# NeuronSynapseVersion3_1.net
KiCad netlist of a schematic drawn in Altium Designer
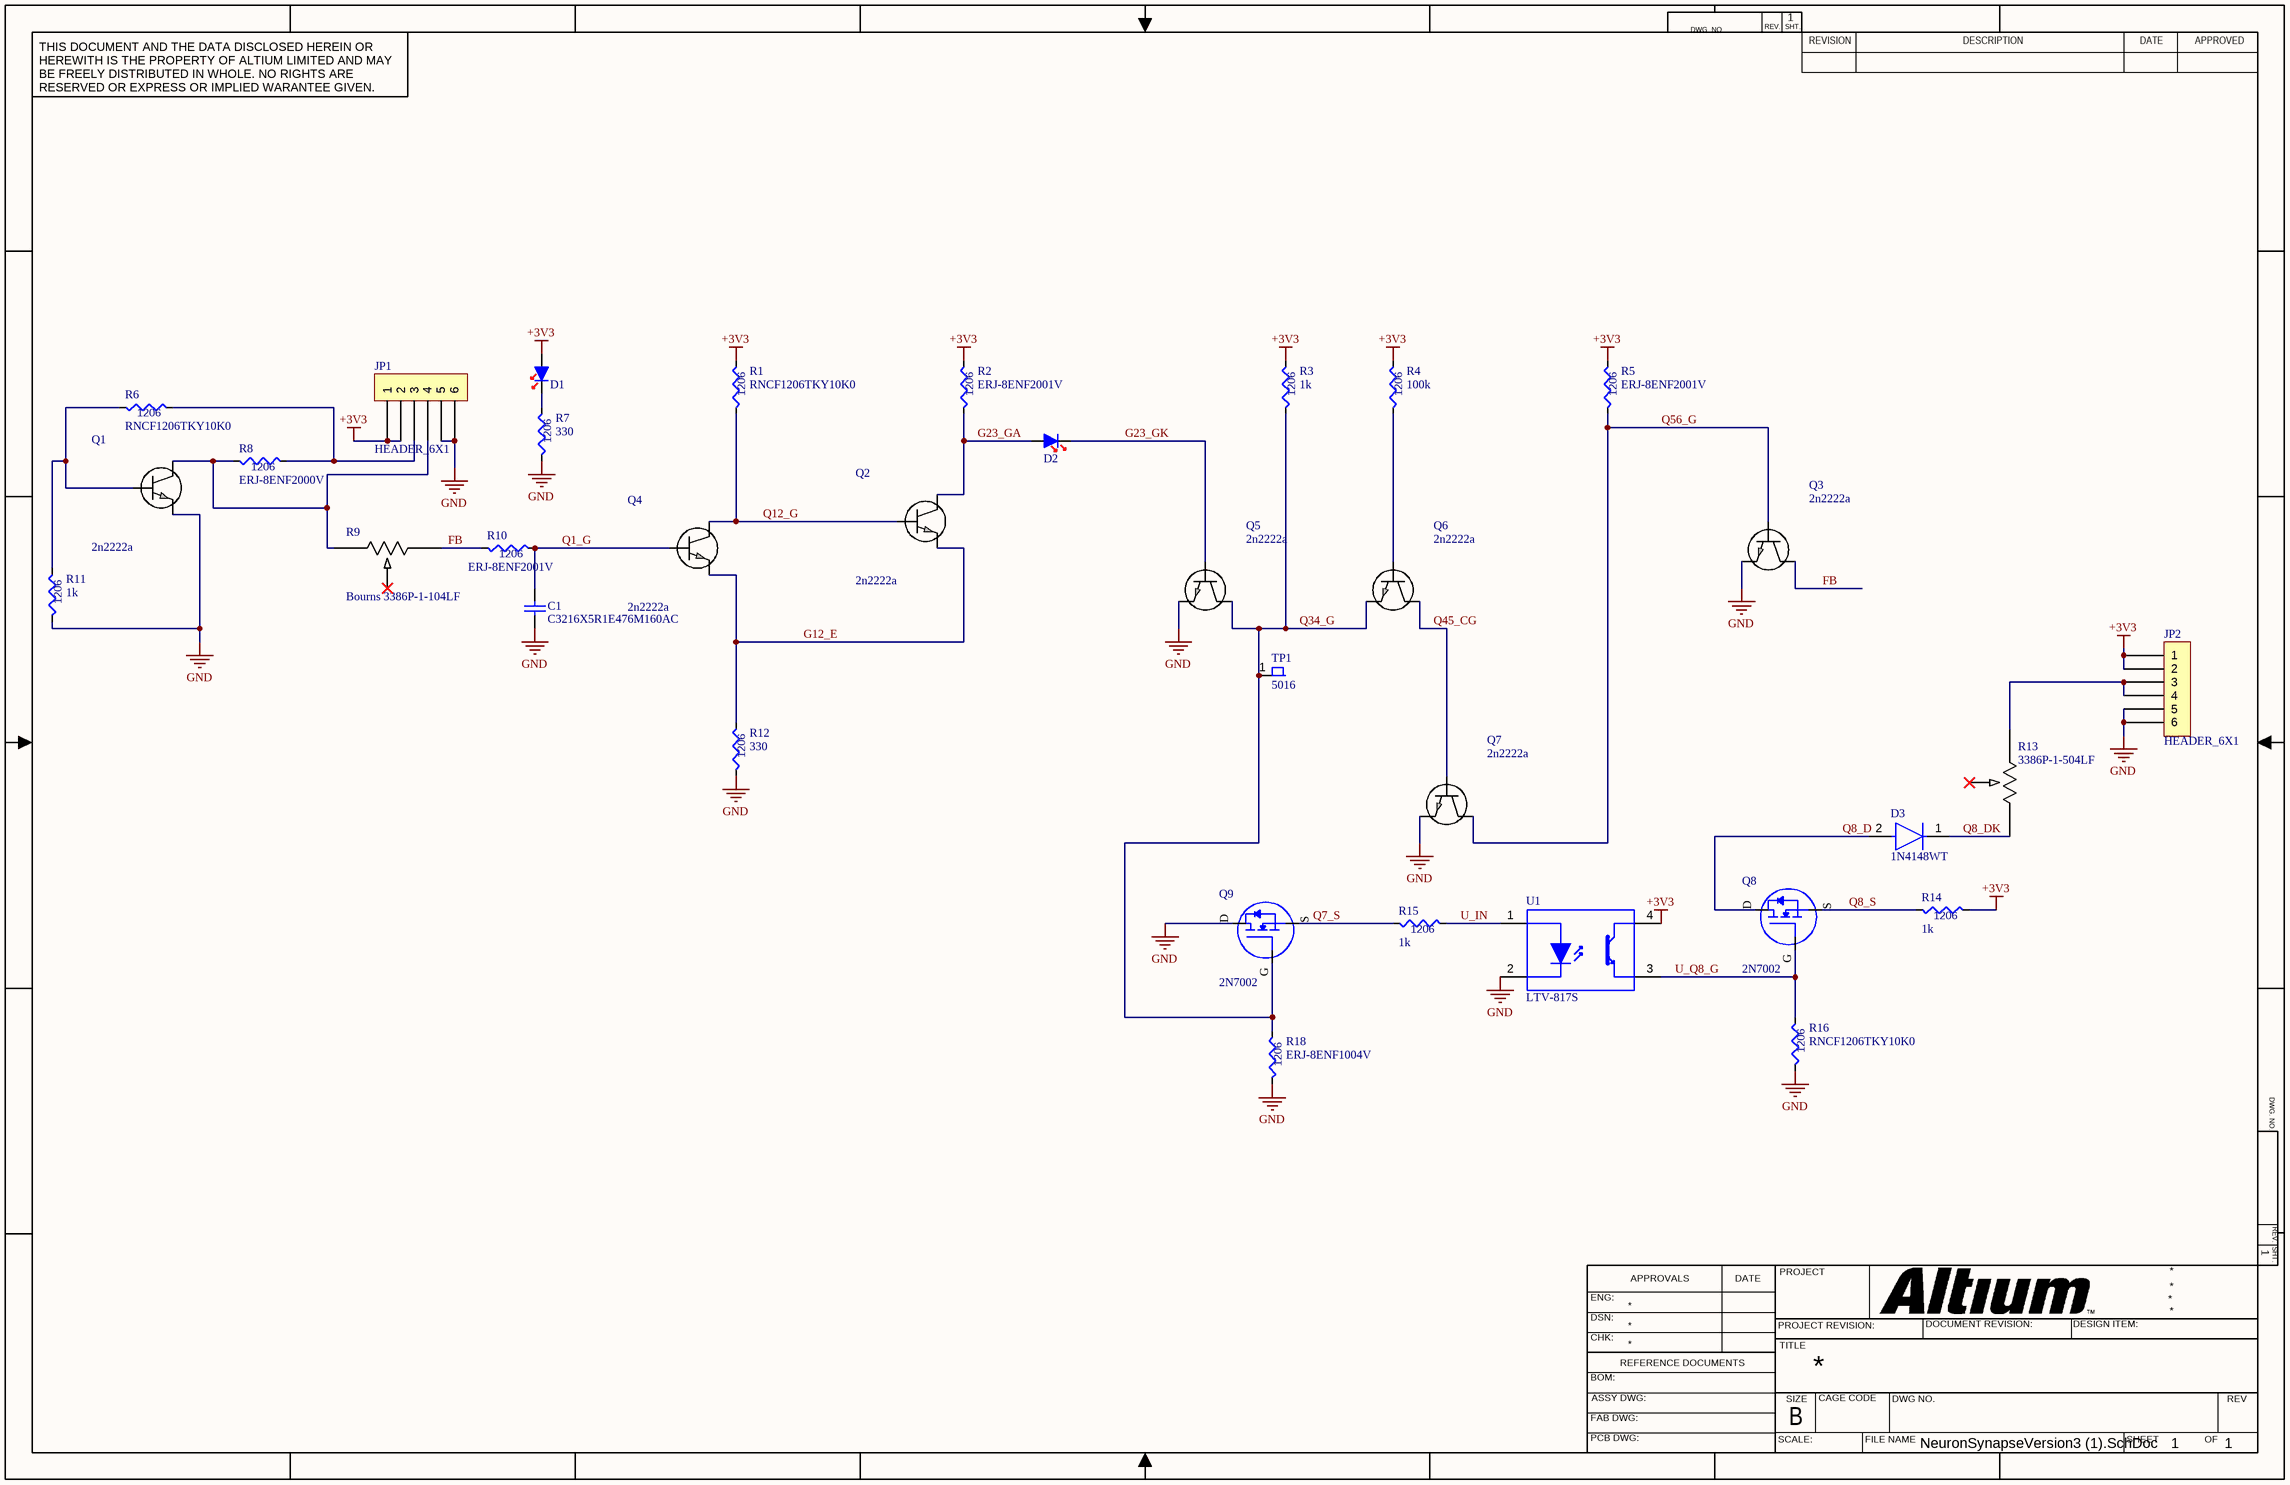
[diagram p0: NeuronSynapseVersion3 (1).SchDoc]

(export (version "E")
  (design (tool "Eeschema 10.0.6"))
  (components
    (comp (ref "C1")
      (value "C3216X5R1E476M160AC")
      (footprint "C1206")
      (description "CER 47uF 25V X5R 1206 2.082mOhm")
      (libsource (lib "") (part "Symbol_1"))
    )
    (comp (ref "D1")
      (value "AA3528SESK/J3")
      (footprint "2-PLCC-RED")
      (description "LED Red 2.2V 20mA")
      (fields (field (name "MADE BY") "Kyle Marino"))
      (libsource (lib "USCRPL") (part "AA3528SESK/J3"))
    )
    (comp (ref "D2")
      (value "AA3528SESK/J3")
      (footprint "2-PLCC-RED")
      (description "LED Red 2.2V 20mA")
      (fields (field (name "MADE BY") "Kyle Marino"))
      (libsource (lib "USCRPL") (part "AA3528SESK/J3"))
    )
    (comp (ref "D3")
      (value "1N4148WT")
      (footprint "FP-017AG-MFG")
      (description "Rectifier Diode, 1 Phase, 1 Element, 0.15A, 100V V(RRM), Silicon")
      (fields (field (name "VOLTAGE") "75V"))
      (libsource (lib "USCRPL") (part "d7152d700b627762746794eb795d46e"))
    )
    (comp (ref "JP1")
      (value "HEADER_6X1")
      (footprint "HEADER1x6PITCH100")
      (description "HEADER VERT 6POS .100 TIN")
      (fields (field (name "MADE BY") "Brennan Swanton") (field (name "REVIEWED BY") "Carter Allen"))
      (libsource (lib "") (part "HEADER_6X1_1"))
    )
    (comp (ref "JP2")
      (value "HEADER_6X1")
      (footprint "HEADER1x6PITCH100")
      (description "HEADER VERT 6POS .100 TIN")
      (fields (field (name "MADE BY") "Brennan Swanton") (field (name "REVIEWED BY") "Carter Allen"))
      (libsource (lib "USCRPL") (part "HEADER_6X1"))
    )
    (comp (ref "Q1")
      (value "2n2222a")
      (footprint "2n2222a-Footprint-1")
      (description "Bipolar (BJT) Transistor NPN 40 V 600 mA 250MHz 625 mW Through Hole TO-92")
      (libsource (lib "USCRPL") (part "2n2222a-Symbol-1"))
    )
    (comp (ref "Q2")
      (value "2n2222a")
      (footprint "2n2222a-Footprint-1")
      (description "Bipolar (BJT) Transistor NPN 40 V 600 mA 250MHz 625 mW Through Hole TO-92")
      (libsource (lib "USCRPL") (part "2n2222a-Symbol-1"))
    )
    (comp (ref "Q3")
      (value "2n2222a")
      (footprint "2n2222a-Footprint-1")
      (description "Bipolar (BJT) Transistor NPN 40 V 600 mA 250MHz 625 mW Through Hole TO-92")
      (libsource (lib "USCRPL") (part "2n2222a-Symbol-1"))
    )
    (comp (ref "Q4")
      (value "2n2222a")
      (footprint "2n2222a-Footprint-1")
      (description "Bipolar (BJT) Transistor NPN 40 V 600 mA 250MHz 625 mW Through Hole TO-92")
      (libsource (lib "USCRPL") (part "2n2222a-Symbol-1"))
    )
    (comp (ref "Q5")
      (value "2n2222a")
      (footprint "2n2222a-Footprint-1")
      (description "Bipolar (BJT) Transistor NPN 40 V 600 mA 250MHz 625 mW Through Hole TO-92")
      (libsource (lib "USCRPL") (part "2n2222a-Symbol-1"))
    )
    (comp (ref "Q6")
      (value "2n2222a")
      (footprint "2n2222a-Footprint-1")
      (description "Bipolar (BJT) Transistor NPN 40 V 600 mA 250MHz 625 mW Through Hole TO-92")
      (libsource (lib "USCRPL") (part "2n2222a-Symbol-1"))
    )
    (comp (ref "Q7")
      (value "2n2222a")
      (footprint "2n2222a-Footprint-1")
      (description "Bipolar (BJT) Transistor NPN 40 V 600 mA 250MHz 625 mW Through Hole TO-92")
      (libsource (lib "USCRPL") (part "2n2222a-Symbol-1"))
    )
    (comp (ref "Q8")
      (value "2N7002")
      (footprint "2N7002")
      (description "MOSFET N-CH 60V 115 mA")
      (fields (field (name "MADE BY") "Kyle Marino"))
      (libsource (lib "USCRPL") (part "2N7002"))
    )
    (comp (ref "Q9")
      (value "2N7002")
      (footprint "2N7002")
      (description "MOSFET N-CH 60V 115 mA")
      (fields (field (name "MADE BY") "Kyle Marino"))
      (libsource (lib "USCRPL") (part "2N7002"))
    )
    (comp (ref "R1")
      (value "RNCF1206TKY10K0")
      (footprint "R1206")
      (description "RES 10K OHM 0.01% 1/4W 1206")
      (fields (field (name "MADE BY") "Jamie Smith"))
      (libsource (lib "USCRPL") (part "Symbol"))
    )
    (comp (ref "R2")
      (value "ERJ-8ENF2001V")
      (footprint "R1206")
      (description "2K OHM 1% 1/4W 1206")
      (fields (field (name "REVIEWED BY") "Carter Allen") (field (name "MADE BY") "Brennan Swanton"))
      (libsource (lib "USCRPL") (part "Symbol"))
    )
    (comp (ref "R3")
      (value "1k")
      (footprint "R1206")
      (description "1K OHM 1% 1/4W 1206")
      (fields (field (name "REVIEWED BY") "Carter Allen") (field (name "MADE BY") "Brennan Swanton"))
      (libsource (lib "USCRPL") (part "Symbol"))
    )
    (comp (ref "R4")
      (value "100k")
      (footprint "R1206")
      (description "100K OHM 1% 1/4W 1206")
      (fields (field (name "REVIEWED BY") "Carter Allen") (field (name "MADE BY") "Brennan Swanton"))
      (libsource (lib "USCRPL") (part "Symbol"))
    )
    (comp (ref "R5")
      (value "ERJ-8ENF2001V")
      (footprint "R1206")
      (description "2K OHM 1% 1/4W 1206")
      (fields (field (name "REVIEWED BY") "Carter Allen") (field (name "MADE BY") "Brennan Swanton"))
      (libsource (lib "USCRPL") (part "Symbol"))
    )
    (comp (ref "R6")
      (value "RNCF1206TKY10K0")
      (footprint "R1206")
      (description "RES 10K OHM 0.01% 1/4W 1206")
      (fields (field (name "MADE BY") "Jamie Smith"))
      (libsource (lib "USCRPL") (part "Symbol"))
    )
    (comp (ref "R7")
      (value "330")
      (footprint "R1206")
      (description "330 OHM 1% 1/4W 1206")
      (fields (field (name "REVIEWED BY") "Carter Allen") (field (name "MADE BY") "Brennan Swanton"))
      (libsource (lib "USCRPL") (part "Symbol"))
    )
    (comp (ref "R8")
      (value "ERJ-8ENF2000V")
      (footprint "R1206")
      (description "200 OHM 1% 1/4W 1206")
      (fields (field (name "MADE BY") "Jamie Smith"))
      (libsource (lib "USCRPL") (part "Symbol"))
    )
    (comp (ref "R9")
      (value "Bourns 3386P-1-104LF")
      (footprint "Bourns 3386P-1-104LF-Footprint-1")
      (description "100 kOhms 0.5W, 1/2W PC Pins Through Hole Trimmer Potentiometer Cermet 1.0 Turn Top Adjustment")
      (libsource (lib "USCRPL") (part "Bourns 3386P-1-104LF-Symbol-1"))
    )
    (comp (ref "R10")
      (value "ERJ-8ENF2001V")
      (footprint "R1206")
      (description "2K OHM 1% 1/4W 1206")
      (fields (field (name "REVIEWED BY") "Carter Allen") (field (name "MADE BY") "Brennan Swanton"))
      (libsource (lib "USCRPL") (part "Symbol"))
    )
    (comp (ref "R11")
      (value "1k")
      (footprint "R1206")
      (description "1K OHM 1% 1/4W 1206")
      (fields (field (name "REVIEWED BY") "Carter Allen") (field (name "MADE BY") "Brennan Swanton"))
      (libsource (lib "USCRPL") (part "Symbol"))
    )
    (comp (ref "R12")
      (value "330")
      (footprint "R1206")
      (description "330 OHM 1% 1/4W 1206")
      (fields (field (name "REVIEWED BY") "Carter Allen") (field (name "MADE BY") "Brennan Swanton"))
      (libsource (lib "USCRPL") (part "Symbol"))
    )
    (comp (ref "R13")
      (value "3386P-1-504LF")
      (footprint "3386P-1-504LF-Footprint-1")
      (description "Cermet Not Linear VERTICAL Trimmer Potentiometer 卤10% 280deg 500mW 85C")
      (libsource (lib "USCRPL") (part "3386P-1-504LF-Symbol-1"))
    )
    (comp (ref "R14")
      (value "1k")
      (footprint "R1206")
      (description "1K OHM 1% 1/4W 1206")
      (fields (field (name "REVIEWED BY") "Carter Allen") (field (name "MADE BY") "Brennan Swanton"))
      (libsource (lib "USCRPL") (part "Symbol"))
    )
    (comp (ref "R15")
      (value "1k")
      (footprint "R1206")
      (description "1K OHM 1% 1/4W 1206")
      (fields (field (name "REVIEWED BY") "Carter Allen") (field (name "MADE BY") "Brennan Swanton"))
      (libsource (lib "USCRPL") (part "Symbol"))
    )
    (comp (ref "R16")
      (value "RNCF1206TKY10K0")
      (footprint "R1206")
      (description "RES 10K OHM 0.01% 1/4W 1206")
      (fields (field (name "MADE BY") "Jamie Smith"))
      (libsource (lib "USCRPL") (part "Symbol"))
    )
    (comp (ref "R18")
      (value "ERJ-8ENF1004V")
      (footprint "R1206")
      (description "1M OHM 1% 1/4W 1206")
      (fields (field (name "MADE BY") "Jamie Smith"))
      (libsource (lib "USCRPL") (part "Symbol"))
    )
    (comp (ref "TP1")
      (value "5016")
      (footprint "5016")
      (description "PC TEST POINT COMPACT SMT")
      (fields (field (name "REVIEWED BY") "Adam Rising"))
      (libsource (lib "USCRPL") (part "5016"))
    )
    (comp (ref "U1")
      (value "LTV-817S")
      (footprint "LTST-LTV-817S-4_V")
      (description "LTV Series Single Channel 35 V 5000 Vrms Transistor Output Optocoupler SMT-DIP-4")
      (fields (field (name "MADE BY") "Diego Gomez Ruiz"))
      (libsource (lib "USCRPL") (part "LTST-LTV-817-4"))
    )
  )
  (nets
    (net (code "1") (name "+3V3") (class "Default")
      (node (ref "D1") (pin "2") (pinfunction "2_2") (pintype "passive"))
      (node (ref "JP1") (pin "1") (pinfunction "1_1") (pintype "passive"))
      (node (ref "JP1") (pin "2") (pinfunction "2_2") (pintype "passive"))
      (node (ref "JP2") (pin "1") (pinfunction "1_1") (pintype "passive"))
      (node (ref "JP2") (pin "2") (pinfunction "2_2") (pintype "passive"))
      (node (ref "R1") (pin "2") (pinfunction "2_2") (pintype "passive"))
      (node (ref "R14") (pin "2") (pinfunction "2_2") (pintype "passive"))
      (node (ref "R2") (pin "2") (pinfunction "2_2") (pintype "passive"))
      (node (ref "R3") (pin "2") (pinfunction "2_2") (pintype "passive"))
      (node (ref "R4") (pin "2") (pinfunction "2_2") (pintype "passive"))
      (node (ref "R5") (pin "2") (pinfunction "2_2") (pintype "passive"))
      (node (ref "U1") (pin "4") (pinfunction "COLLECTOR_4") (pintype "passive"))
    )
    (net (code "2") (name "/FB") (class "Default")
      (node (ref "Q3") (pin "3") (pinfunction "C_3") (pintype "passive"))
      (node (ref "R10") (pin "1") (pinfunction "1_1") (pintype "passive"))
      (node (ref "R9") (pin "1") (pinfunction "1_1") (pintype "passive"))
    )
    (net (code "3") (name "/G12_E") (class "Default")
      (node (ref "Q2") (pin "1") (pinfunction "E_1") (pintype "passive"))
      (node (ref "Q4") (pin "1") (pinfunction "E_1") (pintype "passive"))
      (node (ref "R12") (pin "2") (pinfunction "2_2") (pintype "passive"))
    )
    (net (code "4") (name "/G23_GA") (class "Default")
      (node (ref "D2") (pin "2") (pinfunction "2_2") (pintype "passive"))
      (node (ref "Q2") (pin "3") (pinfunction "C_3") (pintype "passive"))
      (node (ref "R2") (pin "1") (pinfunction "1_1") (pintype "passive"))
    )
    (net (code "5") (name "/G23_GK") (class "Default")
      (node (ref "D2") (pin "1") (pinfunction "1_1") (pintype "passive"))
      (node (ref "Q5") (pin "2") (pinfunction "B_2") (pintype "passive"))
    )
    (net (code "6") (name "/Q1_G") (class "Default")
      (node (ref "C1") (pin "2") (pinfunction "2_2") (pintype "passive"))
      (node (ref "Q4") (pin "2") (pinfunction "B_2") (pintype "passive"))
      (node (ref "R10") (pin "2") (pinfunction "2_2") (pintype "passive"))
    )
    (net (code "7") (name "/Q7_S") (class "Default")
      (node (ref "Q9") (pin "2") (pinfunction "S_2") (pintype "passive"))
      (node (ref "R15") (pin "1") (pinfunction "1_1") (pintype "passive"))
    )
    (net (code "8") (name "/Q8_D") (class "Default")
      (node (ref "D3") (pin "2") (pinfunction "A_2") (pintype "passive"))
      (node (ref "Q8") (pin "3") (pinfunction "D_3") (pintype "passive"))
    )
    (net (code "9") (name "/Q8_DK") (class "Default")
      (node (ref "D3") (pin "1") (pinfunction "C_1") (pintype "passive"))
      (node (ref "R13") (pin "1") (pinfunction "1_1") (pintype "passive"))
    )
    (net (code "10") (name "/Q8_S") (class "Default")
      (node (ref "Q8") (pin "2") (pinfunction "S_2") (pintype "passive"))
      (node (ref "R14") (pin "1") (pinfunction "1_1") (pintype "passive"))
    )
    (net (code "11") (name "/Q12_G") (class "Default")
      (node (ref "Q2") (pin "2") (pinfunction "B_2") (pintype "passive"))
      (node (ref "Q4") (pin "3") (pinfunction "C_3") (pintype "passive"))
      (node (ref "R1") (pin "1") (pinfunction "1_1") (pintype "passive"))
    )
    (net (code "12") (name "/Q34_G") (class "Default")
      (node (ref "Q5") (pin "3") (pinfunction "C_3") (pintype "passive"))
      (node (ref "Q6") (pin "1") (pinfunction "E_1") (pintype "passive"))
      (node (ref "Q9") (pin "1") (pinfunction "G_1") (pintype "passive"))
      (node (ref "R18") (pin "2") (pinfunction "2_2") (pintype "passive"))
      (node (ref "R3") (pin "1") (pinfunction "1_1") (pintype "passive"))
      (node (ref "TP1") (pin "1") (pinfunction "1_1") (pintype "passive"))
    )
    (net (code "13") (name "/Q45_CG") (class "Default")
      (node (ref "Q6") (pin "3") (pinfunction "C_3") (pintype "passive"))
      (node (ref "Q7") (pin "2") (pinfunction "B_2") (pintype "passive"))
    )
    (net (code "14") (name "/Q56_G") (class "Default")
      (node (ref "Q3") (pin "2") (pinfunction "B_2") (pintype "passive"))
      (node (ref "Q7") (pin "3") (pinfunction "C_3") (pintype "passive"))
      (node (ref "R5") (pin "1") (pinfunction "1_1") (pintype "passive"))
    )
    (net (code "15") (name "/U_IN") (class "Default")
      (node (ref "R15") (pin "2") (pinfunction "2_2") (pintype "passive"))
      (node (ref "U1") (pin "1") (pinfunction "ANODE_1") (pintype "passive"))
    )
    (net (code "16") (name "/U_Q8_G") (class "Default")
      (node (ref "Q8") (pin "1") (pinfunction "G_1") (pintype "passive"))
      (node (ref "R16") (pin "2") (pinfunction "2_2") (pintype "passive"))
      (node (ref "U1") (pin "3") (pinfunction "EMITTER_3") (pintype "passive"))
    )
    (net (code "17") (name "GND") (class "Default")
      (node (ref "C1") (pin "1") (pinfunction "1_1") (pintype "passive"))
      (node (ref "JP1") (pin "5") (pinfunction "5_5") (pintype "passive"))
      (node (ref "JP1") (pin "6") (pinfunction "6_6") (pintype "passive"))
      (node (ref "JP2") (pin "5") (pinfunction "5_5") (pintype "passive"))
      (node (ref "JP2") (pin "6") (pinfunction "6_6") (pintype "passive"))
      (node (ref "Q1") (pin "1") (pinfunction "E_1") (pintype "passive"))
      (node (ref "Q3") (pin "1") (pinfunction "E_1") (pintype "passive"))
      (node (ref "Q5") (pin "1") (pinfunction "E_1") (pintype "passive"))
      (node (ref "Q7") (pin "1") (pinfunction "E_1") (pintype "passive"))
      (node (ref "Q9") (pin "3") (pinfunction "D_3") (pintype "passive"))
      (node (ref "R11") (pin "1") (pinfunction "1_1") (pintype "passive"))
      (node (ref "R12") (pin "1") (pinfunction "1_1") (pintype "passive"))
      (node (ref "R16") (pin "1") (pinfunction "1_1") (pintype "passive"))
      (node (ref "R18") (pin "1") (pinfunction "1_1") (pintype "passive"))
      (node (ref "R7") (pin "1") (pinfunction "1_1") (pintype "passive"))
      (node (ref "U1") (pin "2") (pinfunction "CATHODE_2") (pintype "passive"))
    )
    (net (code "18") (name "Net-(D1-Pad1)") (class "Default")
      (node (ref "D1") (pin "1") (pinfunction "1_1") (pintype "passive"))
      (node (ref "R7") (pin "2") (pinfunction "2_2") (pintype "passive"))
    )
    (net (code "19") (name "Net-(JP1-Pad3)") (class "Default")
      (node (ref "JP1") (pin "3") (pinfunction "3_3") (pintype "passive"))
      (node (ref "R6") (pin "2") (pinfunction "2_2") (pintype "passive"))
      (node (ref "R8") (pin "2") (pinfunction "2_2") (pintype "passive"))
    )
    (net (code "20") (name "Net-(JP2-Pad3)") (class "Default")
      (node (ref "JP2") (pin "3") (pinfunction "3_3") (pintype "passive"))
      (node (ref "JP2") (pin "4") (pinfunction "4_4") (pintype "passive"))
      (node (ref "R13") (pin "3") (pinfunction "3_3") (pintype "passive"))
    )
    (net (code "21") (name "Net-(Q1-B)") (class "Default")
      (node (ref "Q1") (pin "2") (pinfunction "B_2") (pintype "passive"))
      (node (ref "R11") (pin "2") (pinfunction "2_2") (pintype "passive"))
      (node (ref "R6") (pin "1") (pinfunction "1_1") (pintype "passive"))
    )
    (net (code "22") (name "Net-(Q1-C)") (class "Default")
      (node (ref "JP1") (pin "4") (pinfunction "4_4") (pintype "passive"))
      (node (ref "Q1") (pin "3") (pinfunction "C_3") (pintype "passive"))
      (node (ref "R8") (pin "1") (pinfunction "1_1") (pintype "passive"))
      (node (ref "R9") (pin "3") (pinfunction "3_3") (pintype "passive"))
    )
    (net (code "23") (name "Net-(Q6-B)") (class "Default")
      (node (ref "Q6") (pin "2") (pinfunction "B_2") (pintype "passive"))
      (node (ref "R4") (pin "1") (pinfunction "1_1") (pintype "passive"))
    )
    (net (code "24") (name "unconnected-(R9-Pad2)") (class "Default")
      (node (ref "R9") (pin "2") (pinfunction "2_2") (pintype "passive+no_connect"))
    )
    (net (code "25") (name "unconnected-(R13-Pad2)") (class "Default")
      (node (ref "R13") (pin "2") (pinfunction "2_2") (pintype "passive+no_connect"))
    )
  )
)
